# Solar_Power_Converter_with_MPPT.net
KiCad netlist of a schematic drawn in Altium Designer
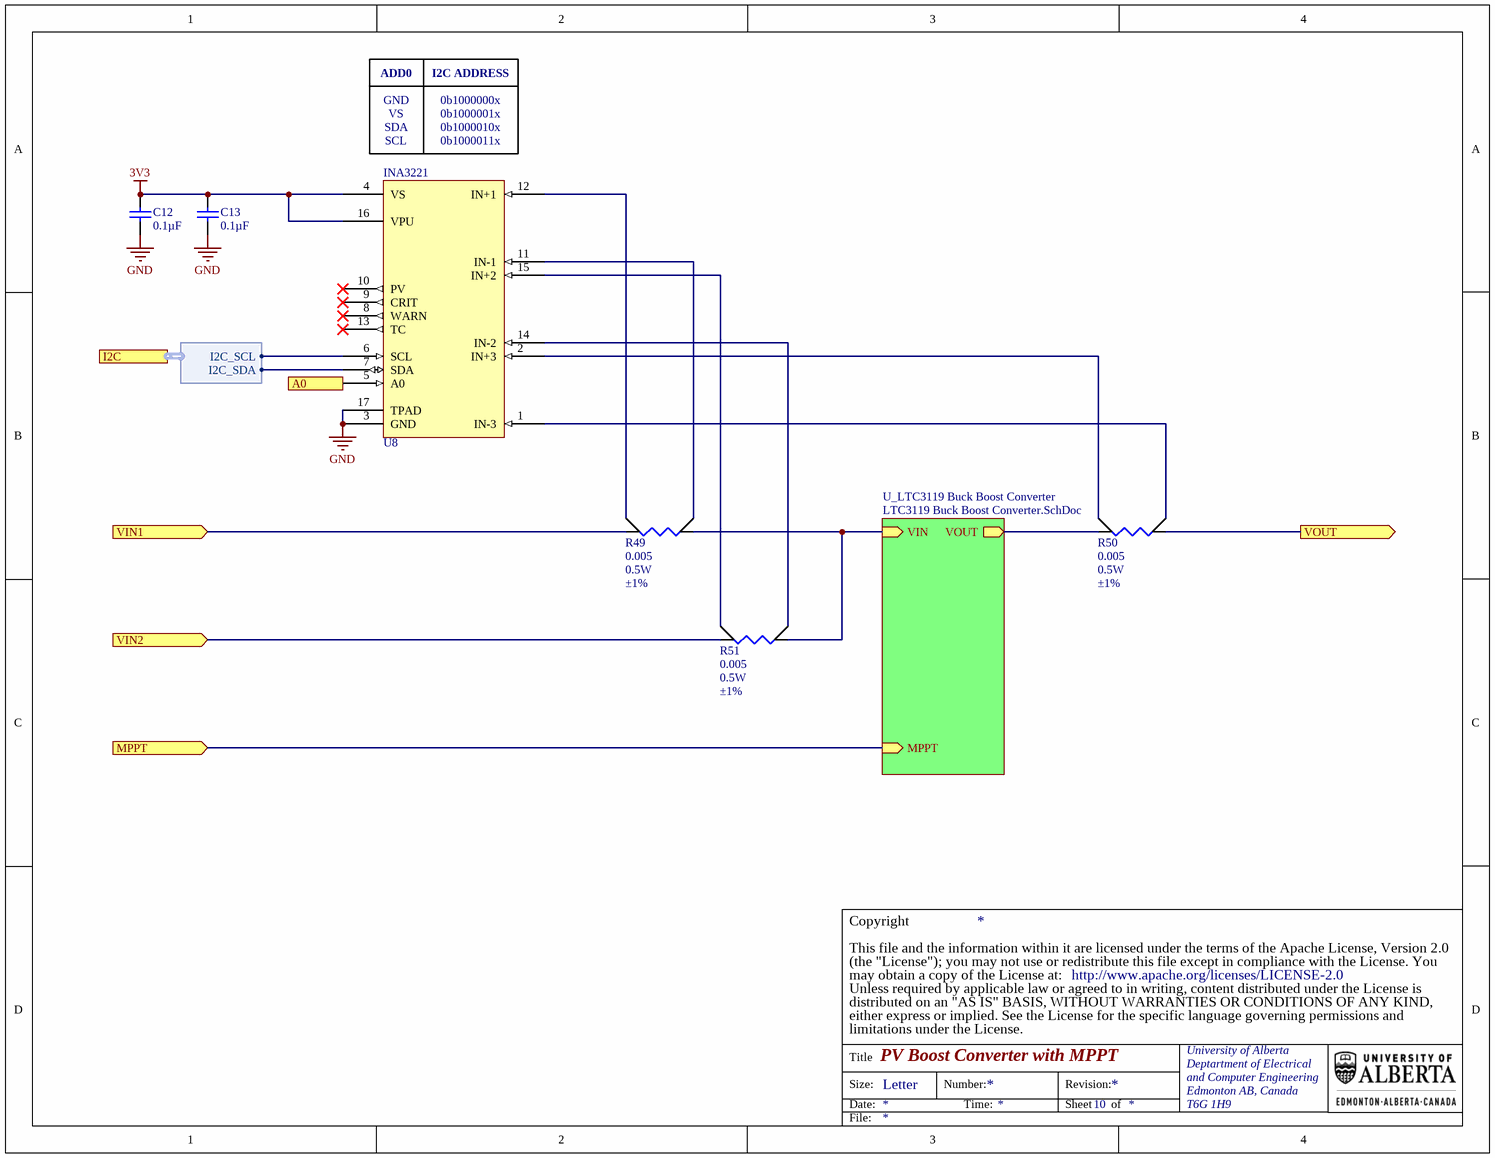
[diagram p0: Solar Power Converter with MPPT.SchDoc]

(export (version "E")
  (design (tool "Eeschema 10.0.6"))
  (components
    (comp (ref "C12")
      (value "0.1µF")
      (footprint "TDK-CGA2B")
      (description "CAP CER 0.1UF 50V X7R 0402")
      (fields
        (field (name "PART NUMBER") "PC-TDK-02259")
        (field (name "MANUFACTURER PART NUMBER") "CGA2B3X7R1H104K050BB")
        (field (name "PUBLISHER") "AlbertaSat")
      )
      (libsource (lib "Database") (part "Cap"))
    )
    (comp (ref "C13")
      (value "0.1µF")
      (footprint "TDK-CGA2B")
      (description "CAP CER 0.1UF 50V X7R 0402")
      (fields
        (field (name "PART NUMBER") "PC-TDK-02259")
        (field (name "MANUFACTURER PART NUMBER") "CGA2B3X7R1H104K050BB")
        (field (name "PUBLISHER") "AlbertaSat")
      )
      (libsource (lib "Database") (part "Cap"))
    )
    (comp (ref "R49")
      (value "0.005")
      (footprint "BRN-CRF0805")
      (description "RES 0.005 OHM 1% 1/2W 0805")
      (fields
        (field (name "POWER - RATED") "0.5W")
        (field (name "TOLERANCE") "±1%")
        (field (name "PART NUMBER") "PR-BRN-00023")
        (field (name "MANUFACTURER PART NUMBER") "CRF0805-FZ-R005ELF")
        (field (name "PUBLISHER") "AlbertaSat")
      )
      (libsource (lib "Database") (part "Res Sense"))
    )
    (comp (ref "R50")
      (value "0.005")
      (footprint "BRN-CRF0805")
      (description "RES 0.005 OHM 1% 1/2W 0805")
      (fields
        (field (name "POWER - RATED") "0.5W")
        (field (name "TOLERANCE") "±1%")
        (field (name "PART NUMBER") "PR-BRN-00023")
        (field (name "MANUFACTURER PART NUMBER") "CRF0805-FZ-R005ELF")
        (field (name "PUBLISHER") "AlbertaSat")
      )
      (libsource (lib "Database") (part "Res Sense"))
    )
    (comp (ref "R51")
      (value "0.005")
      (footprint "BRN-CRF0805")
      (description "RES 0.005 OHM 1% 1/2W 0805")
      (fields
        (field (name "POWER - RATED") "0.5W")
        (field (name "TOLERANCE") "±1%")
        (field (name "PART NUMBER") "PR-BRN-00023")
        (field (name "MANUFACTURER PART NUMBER") "CRF0805-FZ-R005ELF")
        (field (name "PUBLISHER") "AlbertaSat")
      )
      (libsource (lib "Database") (part "Res Sense"))
    )
    (comp (ref "U8")
      (value "INA3221")
      (footprint "TI-RGV")
      (description "IC CURRENT SHUNT MONITOR 16VQFN")
      (fields (field (name "PART NUMBER") "39") (field (name "MANUFACTURER PART NUMBER") "INA3221AQRGVRQ1"))
      (libsource (lib "Database") (part "INA3221AQRGV"))
    )
  )
  (nets
    (net (code "2") (name "/A0") (class "Default")
      (node (ref "U8") (pin "5") (pinfunction "A0_5") (pintype "input"))
    )
    (net (code "3") (name "/I2C_SCL") (class "Default")
      (node (ref "U8") (pin "6") (pinfunction "SCL_6") (pintype "input"))
    )
    (net (code "4") (name "/I2C_SDA") (class "Default")
      (node (ref "U8") (pin "7") (pinfunction "SDA_7") (pintype "bidirectional"))
    )
    (net (code "6") (name "/VIN") (class "Default")
      (node (ref "R49") (pin "1") (pinfunction "I1_1") (pintype "passive"))
      (node (ref "R51") (pin "1") (pinfunction "I1_1") (pintype "passive"))
    )
    (net (code "7") (name "/VIN1") (class "Default")
      (node (ref "R49") (pin "2") (pinfunction "I2_2") (pintype "passive"))
    )
    (net (code "8") (name "/VIN2") (class "Default")
      (node (ref "R51") (pin "2") (pinfunction "I2_2") (pintype "passive"))
    )
    (net (code "9") (name "/VOUT") (class "Default")
      (node (ref "R50") (pin "1") (pinfunction "I1_1") (pintype "passive"))
    )
    (net (code "10") (name "/VOUT_1") (class "Default")
      (node (ref "R50") (pin "2") (pinfunction "I2_2") (pintype "passive"))
    )
    (net (code "12") (name "3V3") (class "Default")
      (node (ref "C12") (pin "2") (pinfunction "2_2") (pintype "passive"))
      (node (ref "C13") (pin "2") (pinfunction "2_2") (pintype "passive"))
      (node (ref "U8") (pin "16") (pinfunction "VPU_16") (pintype "power_in"))
      (node (ref "U8") (pin "4") (pinfunction "VS_4") (pintype "power_in"))
    )
    (net (code "13") (name "GND") (class "Default")
      (node (ref "C12") (pin "1") (pinfunction "1_1") (pintype "passive"))
      (node (ref "C13") (pin "1") (pinfunction "1_1") (pintype "passive"))
      (node (ref "U8") (pin "17") (pinfunction "TPAD_17") (pintype "power_in"))
      (node (ref "U8") (pin "3") (pinfunction "GND_3") (pintype "power_in"))
    )
    (net (code "14") (name "Net-(R49-S1)") (class "Default")
      (node (ref "R49") (pin "4") (pinfunction "S1_4") (pintype "passive"))
      (node (ref "U8") (pin "11") (pinfunction "IN-1_11") (pintype "input"))
    )
    (net (code "15") (name "Net-(R49-S2)") (class "Default")
      (node (ref "R49") (pin "3") (pinfunction "S2_3") (pintype "passive"))
      (node (ref "U8") (pin "12") (pinfunction "IN+1_12") (pintype "input"))
    )
    (net (code "16") (name "Net-(R50-S1)") (class "Default")
      (node (ref "R50") (pin "4") (pinfunction "S1_4") (pintype "passive"))
      (node (ref "U8") (pin "1") (pinfunction "IN-3_1") (pintype "input"))
    )
    (net (code "17") (name "Net-(R50-S2)") (class "Default")
      (node (ref "R50") (pin "3") (pinfunction "S2_3") (pintype "passive"))
      (node (ref "U8") (pin "2") (pinfunction "IN+3_2") (pintype "input"))
    )
    (net (code "18") (name "Net-(R51-S1)") (class "Default")
      (node (ref "R51") (pin "4") (pinfunction "S1_4") (pintype "passive"))
      (node (ref "U8") (pin "14") (pinfunction "IN-2_14") (pintype "input"))
    )
    (net (code "19") (name "Net-(R51-S2)") (class "Default")
      (node (ref "R51") (pin "3") (pinfunction "S2_3") (pintype "passive"))
      (node (ref "U8") (pin "15") (pinfunction "IN+2_15") (pintype "input"))
    )
    (net (code "20") (name "unconnected-(U8-CRIT-Pad9)") (class "Default")
      (node (ref "U8") (pin "9") (pinfunction "CRIT_9") (pintype "output+no_connect"))
    )
    (net (code "21") (name "unconnected-(U8-PV-Pad10)") (class "Default")
      (node (ref "U8") (pin "10") (pinfunction "PV_10") (pintype "output+no_connect"))
    )
    (net (code "22") (name "unconnected-(U8-TC-Pad13)") (class "Default")
      (node (ref "U8") (pin "13") (pinfunction "TC_13") (pintype "output+no_connect"))
    )
    (net (code "23") (name "unconnected-(U8-WARN-Pad8)") (class "Default")
      (node (ref "U8") (pin "8") (pinfunction "WARN_8") (pintype "output+no_connect"))
    )
  )
)
